# Nodino-Base2.net
KiCad netlist of a schematic drawn in EAGLE
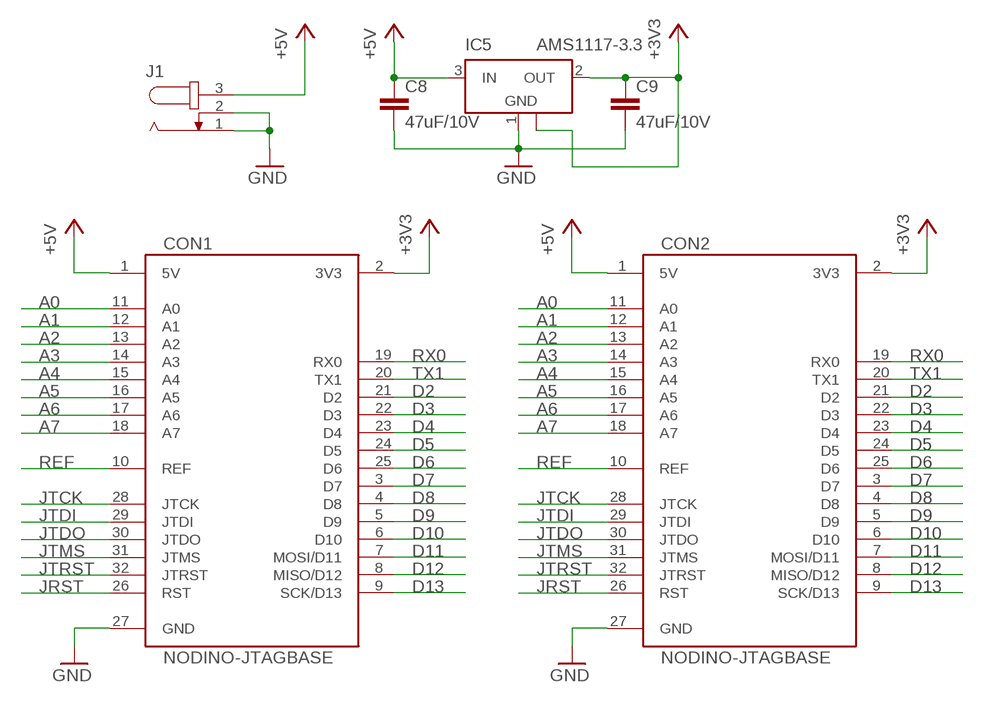
[diagram p0: schematic, sheet 1]

(export (version "E")
  (design (tool "Eeschema 10.0.6"))
  (components
    (comp (ref "C8")
      (value "47uF/10V")
      (footprint "eagle-import:C3225")
      (libsource (lib "eagle-import") (part "C-EUC3225"))
    )
    (comp (ref "C9")
      (value "47uF/10V")
      (footprint "eagle-import:C3225")
      (libsource (lib "eagle-import") (part "C-EUC3225"))
    )
    (comp (ref "CON1")
      (value "NODINO-JTAGBASE")
      (footprint "eagle-import:NODINO-JTAG-BASE")
      (libsource (lib "eagle-import") (part "NODINO-JTAGBASE"))
    )
    (comp (ref "CON2")
      (value "NODINO-JTAGBASE")
      (footprint "eagle-import:NODINO-JTAG-BASE")
      (libsource (lib "eagle-import") (part "NODINO-JTAGBASE"))
    )
    (comp (ref "IC5")
      (value "AMS1117-3.3")
      (footprint "eagle-import:SOT223")
      (libsource (lib "eagle-import") (part "AMS1117-3.3"))
    )
    (comp (ref "J1")
      (value "JACK-PLUG0")
      (footprint "eagle-import:SPC4077")
      (libsource (lib "eagle-import") (part "JACK-PLUG0"))
    )
  )
  (nets
    (net (code "1") (name "+3V3") (class "Default")
      (node (ref "C9") (pin "1") (pinfunction "1_1") (pintype "passive"))
      (node (ref "CON1") (pin "2") (pinfunction "3V3_2") (pintype "bidirectional"))
      (node (ref "CON2") (pin "2") (pinfunction "3V3_2") (pintype "bidirectional"))
      (node (ref "IC5") (pin "2") (pinfunction "OUT_2") (pintype "output"))
      (node (ref "IC5") (pin "4") (pinfunction "GND_4") (pintype "power_in"))
    )
    (net (code "2") (name "+5V") (class "Default")
      (node (ref "C8") (pin "1") (pinfunction "1_1") (pintype "passive"))
      (node (ref "CON1") (pin "1") (pinfunction "5V_1") (pintype "bidirectional"))
      (node (ref "CON2") (pin "1") (pinfunction "5V_1") (pintype "bidirectional"))
      (node (ref "IC5") (pin "3") (pinfunction "IN_3") (pintype "input"))
      (node (ref "J1") (pin "3") (pinfunction "3_3") (pintype "passive"))
    )
    (net (code "3") (name "/A0") (class "Default")
      (node (ref "CON1") (pin "11") (pinfunction "A0_11") (pintype "bidirectional"))
      (node (ref "CON2") (pin "11") (pinfunction "A0_11") (pintype "bidirectional"))
    )
    (net (code "4") (name "/A1") (class "Default")
      (node (ref "CON1") (pin "12") (pinfunction "A1_12") (pintype "bidirectional"))
      (node (ref "CON2") (pin "12") (pinfunction "A1_12") (pintype "bidirectional"))
    )
    (net (code "5") (name "/A2") (class "Default")
      (node (ref "CON1") (pin "13") (pinfunction "A2_13") (pintype "bidirectional"))
      (node (ref "CON2") (pin "13") (pinfunction "A2_13") (pintype "bidirectional"))
    )
    (net (code "6") (name "/A3") (class "Default")
      (node (ref "CON1") (pin "14") (pinfunction "A3_14") (pintype "bidirectional"))
      (node (ref "CON2") (pin "14") (pinfunction "A3_14") (pintype "bidirectional"))
    )
    (net (code "7") (name "/A4") (class "Default")
      (node (ref "CON1") (pin "15") (pinfunction "A4_15") (pintype "bidirectional"))
      (node (ref "CON2") (pin "15") (pinfunction "A4_15") (pintype "bidirectional"))
    )
    (net (code "8") (name "/A5") (class "Default")
      (node (ref "CON1") (pin "16") (pinfunction "A5_16") (pintype "bidirectional"))
      (node (ref "CON2") (pin "16") (pinfunction "A5_16") (pintype "bidirectional"))
    )
    (net (code "9") (name "/A6") (class "Default")
      (node (ref "CON1") (pin "17") (pinfunction "A6_17") (pintype "bidirectional"))
      (node (ref "CON2") (pin "17") (pinfunction "A6_17") (pintype "bidirectional"))
    )
    (net (code "10") (name "/A7") (class "Default")
      (node (ref "CON1") (pin "18") (pinfunction "A7_18") (pintype "bidirectional"))
      (node (ref "CON2") (pin "18") (pinfunction "A7_18") (pintype "bidirectional"))
    )
    (net (code "11") (name "/D2") (class "Default")
      (node (ref "CON1") (pin "21") (pinfunction "D2_21") (pintype "bidirectional"))
      (node (ref "CON2") (pin "21") (pinfunction "D2_21") (pintype "bidirectional"))
    )
    (net (code "12") (name "/D3") (class "Default")
      (node (ref "CON1") (pin "22") (pinfunction "D3_22") (pintype "bidirectional"))
      (node (ref "CON2") (pin "22") (pinfunction "D3_22") (pintype "bidirectional"))
    )
    (net (code "13") (name "/D4") (class "Default")
      (node (ref "CON1") (pin "23") (pinfunction "D4_23") (pintype "bidirectional"))
      (node (ref "CON2") (pin "23") (pinfunction "D4_23") (pintype "bidirectional"))
    )
    (net (code "14") (name "/D5") (class "Default")
      (node (ref "CON1") (pin "24") (pinfunction "D5_24") (pintype "bidirectional"))
      (node (ref "CON2") (pin "24") (pinfunction "D5_24") (pintype "bidirectional"))
    )
    (net (code "15") (name "/D6") (class "Default")
      (node (ref "CON1") (pin "25") (pinfunction "D6_25") (pintype "bidirectional"))
      (node (ref "CON2") (pin "25") (pinfunction "D6_25") (pintype "bidirectional"))
    )
    (net (code "16") (name "/D7") (class "Default")
      (node (ref "CON1") (pin "3") (pinfunction "D7_3") (pintype "bidirectional"))
      (node (ref "CON2") (pin "3") (pinfunction "D7_3") (pintype "bidirectional"))
    )
    (net (code "17") (name "/D8") (class "Default")
      (node (ref "CON1") (pin "4") (pinfunction "D8_4") (pintype "bidirectional"))
      (node (ref "CON2") (pin "4") (pinfunction "D8_4") (pintype "bidirectional"))
    )
    (net (code "18") (name "/D9") (class "Default")
      (node (ref "CON1") (pin "5") (pinfunction "D9_5") (pintype "bidirectional"))
      (node (ref "CON2") (pin "5") (pinfunction "D9_5") (pintype "bidirectional"))
    )
    (net (code "19") (name "/D10") (class "Default")
      (node (ref "CON1") (pin "6") (pinfunction "D10_6") (pintype "bidirectional"))
      (node (ref "CON2") (pin "6") (pinfunction "D10_6") (pintype "bidirectional"))
    )
    (net (code "20") (name "/D11") (class "Default")
      (node (ref "CON1") (pin "7") (pinfunction "MOSI/D11_7") (pintype "bidirectional"))
      (node (ref "CON2") (pin "7") (pinfunction "MOSI/D11_7") (pintype "bidirectional"))
    )
    (net (code "21") (name "/D12") (class "Default")
      (node (ref "CON1") (pin "8") (pinfunction "MISO/D12_8") (pintype "bidirectional"))
      (node (ref "CON2") (pin "8") (pinfunction "MISO/D12_8") (pintype "bidirectional"))
    )
    (net (code "22") (name "/D13") (class "Default")
      (node (ref "CON1") (pin "9") (pinfunction "SCK/D13_9") (pintype "bidirectional"))
      (node (ref "CON2") (pin "9") (pinfunction "SCK/D13_9") (pintype "bidirectional"))
    )
    (net (code "23") (name "/JRST") (class "Default")
      (node (ref "CON1") (pin "26") (pinfunction "RST_26") (pintype "bidirectional"))
      (node (ref "CON2") (pin "26") (pinfunction "RST_26") (pintype "bidirectional"))
    )
    (net (code "24") (name "/JTCK") (class "Default")
      (node (ref "CON1") (pin "28") (pinfunction "JTCK_28") (pintype "bidirectional"))
      (node (ref "CON2") (pin "28") (pinfunction "JTCK_28") (pintype "bidirectional"))
    )
    (net (code "25") (name "/JTDI") (class "Default")
      (node (ref "CON1") (pin "29") (pinfunction "JTDI_29") (pintype "bidirectional"))
      (node (ref "CON2") (pin "29") (pinfunction "JTDI_29") (pintype "bidirectional"))
    )
    (net (code "26") (name "/JTDO") (class "Default")
      (node (ref "CON1") (pin "30") (pinfunction "JTDO_30") (pintype "bidirectional"))
      (node (ref "CON2") (pin "30") (pinfunction "JTDO_30") (pintype "bidirectional"))
    )
    (net (code "27") (name "/JTMS") (class "Default")
      (node (ref "CON1") (pin "31") (pinfunction "JTMS_31") (pintype "bidirectional"))
      (node (ref "CON2") (pin "31") (pinfunction "JTMS_31") (pintype "bidirectional"))
    )
    (net (code "28") (name "/JTRST") (class "Default")
      (node (ref "CON1") (pin "32") (pinfunction "JTRST_32") (pintype "bidirectional"))
      (node (ref "CON2") (pin "32") (pinfunction "JTRST_32") (pintype "bidirectional"))
    )
    (net (code "29") (name "/REF") (class "Default")
      (node (ref "CON1") (pin "10") (pinfunction "REF_10") (pintype "bidirectional"))
      (node (ref "CON2") (pin "10") (pinfunction "REF_10") (pintype "bidirectional"))
    )
    (net (code "30") (name "/RX0") (class "Default")
      (node (ref "CON1") (pin "19") (pinfunction "RX0_19") (pintype "bidirectional"))
      (node (ref "CON2") (pin "19") (pinfunction "RX0_19") (pintype "bidirectional"))
    )
    (net (code "31") (name "/TX1") (class "Default")
      (node (ref "CON1") (pin "20") (pinfunction "TX1_20") (pintype "bidirectional"))
      (node (ref "CON2") (pin "20") (pinfunction "TX1_20") (pintype "bidirectional"))
    )
    (net (code "32") (name "GND") (class "Default")
      (node (ref "C8") (pin "2") (pinfunction "2_2") (pintype "passive"))
      (node (ref "C9") (pin "2") (pinfunction "2_2") (pintype "passive"))
      (node (ref "CON1") (pin "27") (pinfunction "GND_27") (pintype "bidirectional"))
      (node (ref "CON2") (pin "27") (pinfunction "GND_27") (pintype "bidirectional"))
      (node (ref "IC5") (pin "1") (pinfunction "GND_1") (pintype "power_in"))
      (node (ref "J1") (pin "1") (pinfunction "1_1") (pintype "passive"))
      (node (ref "J1") (pin "2") (pinfunction "2_2") (pintype "passive"))
    )
  )
)
